# Relay_Board_R2.net
KiCad netlist of a schematic drawn in EAGLE
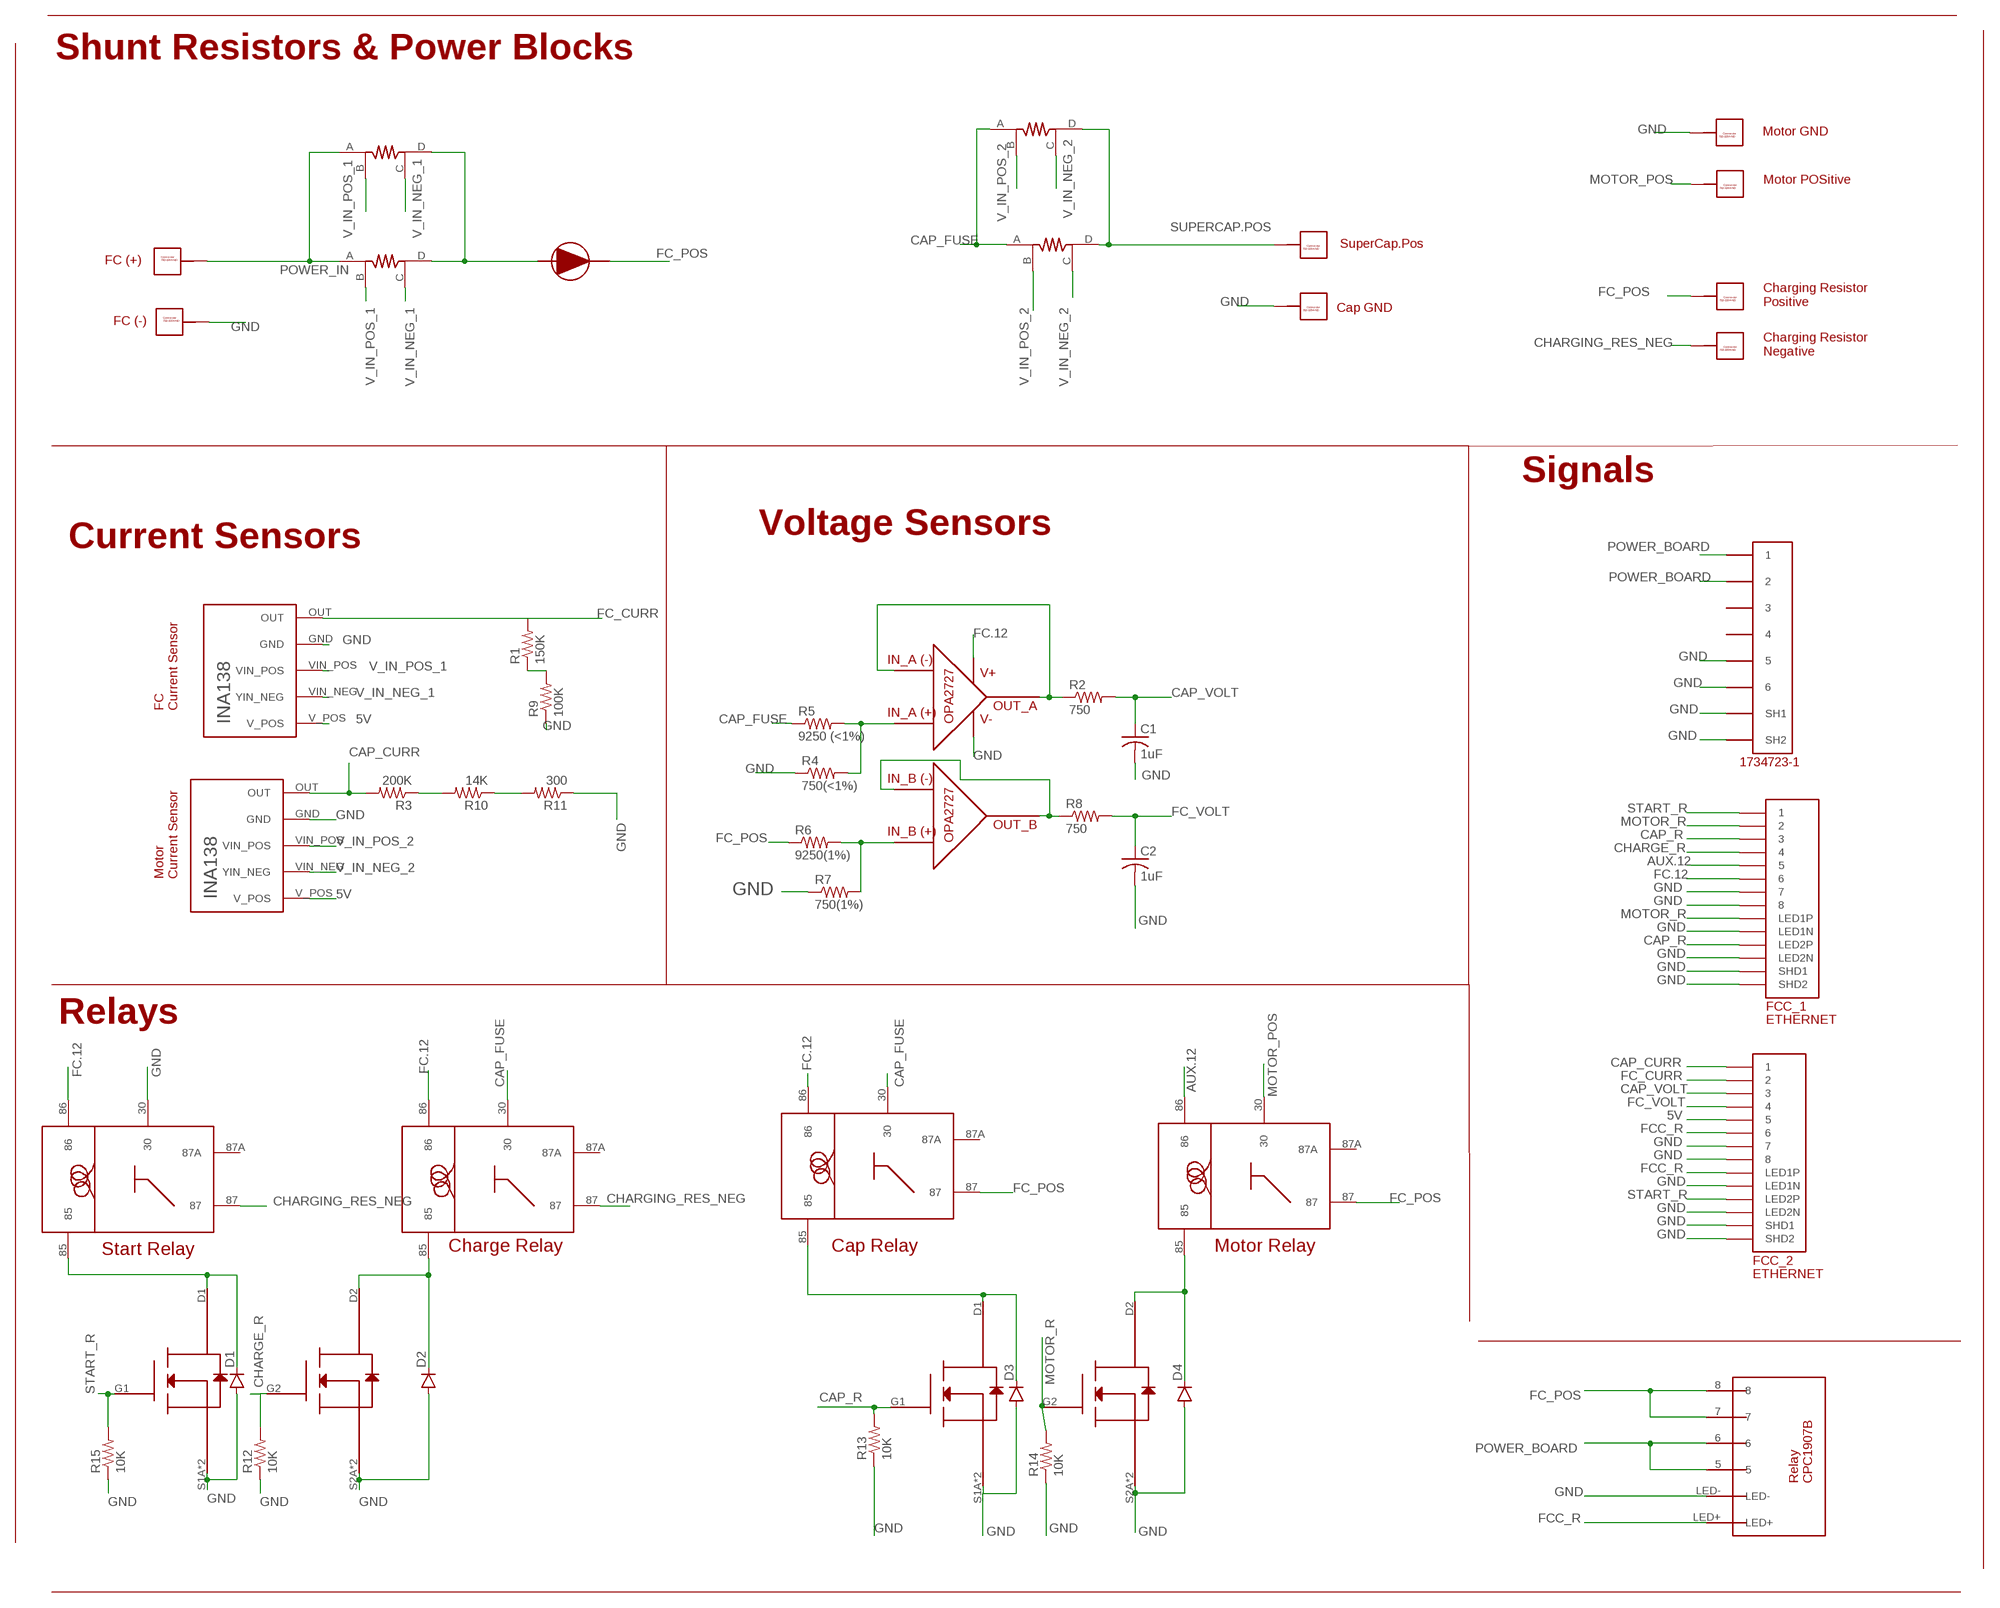
[diagram p0: schematic, sheet 1]

(export (version "E")
  (design (tool "Eeschema 10.0.6"))
  (components
    (comp (ref "C1")
      (value "1uF")
      (footprint "eagle-import:C0805")
      (libsource (lib "eagle-import") (part "C-USC0805"))
    )
    (comp (ref "C2")
      (value "1uF")
      (footprint "eagle-import:C0805")
      (libsource (lib "eagle-import") (part "C-USC0805"))
    )
    (comp (ref "CAP.GND")
      (value "732-3204-ND_CONNECTOR")
      (footprint "eagle-import:732-3204-ND")
      (libsource (lib "eagle-import") (part "732-3204-ND_CONNECTOR"))
    )
    (comp (ref "CAP.POS")
      (value "732-3204-ND_CONNECTOR")
      (footprint "eagle-import:732-3204-ND")
      (libsource (lib "eagle-import") (part "732-3204-ND_CONNECTOR"))
    )
    (comp (ref "CAP.RELAY")
      (value "VCF4-1000")
      (footprint "eagle-import:VCF4-1000")
      (libsource (lib "eagle-import") (part "VCF4-1000"))
    )
    (comp (ref "CAP.SHUNT.1")
      (value "SHUNT_RESISTOR_CSM3637")
      (footprint "eagle-import:CSM3637")
      (libsource (lib "eagle-import") (part "SHUNT_RESISTOR_CSM3637"))
    )
    (comp (ref "CAP.SHUNT.2")
      (value "SHUNT_RESISTOR_CSM3637")
      (footprint "eagle-import:CSM3637")
      (libsource (lib "eagle-import") (part "SHUNT_RESISTOR_CSM3637"))
    )
    (comp (ref "CHARGE_RELAY")
      (value "VCF4-1000")
      (footprint "eagle-import:VCF4-1000")
      (libsource (lib "eagle-import") (part "VCF4-1000"))
    )
    (comp (ref "D1")
      (value "DIODESOD123")
      (footprint "eagle-import:SOD-123")
      (libsource (lib "eagle-import") (part "DIODESOD123"))
    )
    (comp (ref "D2")
      (value "DIODESOD123")
      (footprint "eagle-import:SOD-123")
      (libsource (lib "eagle-import") (part "DIODESOD123"))
    )
    (comp (ref "D3")
      (value "DIODESOD123")
      (footprint "eagle-import:SOD-123")
      (libsource (lib "eagle-import") (part "DIODESOD123"))
    )
    (comp (ref "D4")
      (value "DIODESOD123")
      (footprint "eagle-import:SOD-123")
      (libsource (lib "eagle-import") (part "DIODESOD123"))
    )
    (comp (ref "FC.CURR.SENSOR")
      (value "TI_INA138")
      (footprint "eagle-import:TI_INA138")
      (libsource (lib "eagle-import") (part "TI_INA138"))
    )
    (comp (ref "FC.GND")
      (value "732-3204-ND_CONNECTOR")
      (footprint "eagle-import:732-3204-ND")
      (libsource (lib "eagle-import") (part "732-3204-ND_CONNECTOR"))
    )
    (comp (ref "FC.POS")
      (value "732-3204-ND_CONNECTOR")
      (footprint "eagle-import:732-3204-ND")
      (libsource (lib "eagle-import") (part "732-3204-ND_CONNECTOR"))
    )
    (comp (ref "FC.SHUNT.1")
      (value "SHUNT_RESISTOR_CSM3637")
      (footprint "eagle-import:CSM3637")
      (libsource (lib "eagle-import") (part "SHUNT_RESISTOR_CSM3637"))
    )
    (comp (ref "FC.SHUNT.2")
      (value "SHUNT_RESISTOR_CSM3637")
      (footprint "eagle-import:CSM3637")
      (libsource (lib "eagle-import") (part "SHUNT_RESISTOR_CSM3637"))
    )
    (comp (ref "FCC_1")
      (value "ETHERNET")
      (footprint "eagle-import:A122645-ND")
      (libsource (lib "eagle-import") (part "ETHERNET"))
    )
    (comp (ref "FCC_2")
      (value "ETHERNET")
      (footprint "eagle-import:A122645-ND")
      (libsource (lib "eagle-import") (part "ETHERNET"))
    )
    (comp (ref "FC_DIODE")
      (value "DIODE-APT60S20BG")
      (footprint "eagle-import:DIODE-APT60S20BG")
      (libsource (lib "eagle-import") (part "DIODE-APT60S20BG"))
    )
    (comp (ref "MOTOR.CURR.SENSOR")
      (value "TI_INA138")
      (footprint "eagle-import:TI_INA138")
      (libsource (lib "eagle-import") (part "TI_INA138"))
    )
    (comp (ref "MOTOR.GROUND")
      (value "732-3204-ND_CONNECTOR")
      (footprint "eagle-import:732-3204-ND")
      (libsource (lib "eagle-import") (part "732-3204-ND_CONNECTOR"))
    )
    (comp (ref "MOTOR.POSITIVE")
      (value "732-3204-ND_CONNECTOR")
      (footprint "eagle-import:732-3204-ND")
      (libsource (lib "eagle-import") (part "732-3204-ND_CONNECTOR"))
    )
    (comp (ref "MOTOR.RELAY")
      (value "VCF4-1000")
      (footprint "eagle-import:VCF4-1000")
      (libsource (lib "eagle-import") (part "VCF4-1000"))
    )
    (comp (ref "R1")
      (value "150K")
      (footprint "eagle-import:R0805")
      (libsource (lib "eagle-import") (part "R-US_R0805"))
    )
    (comp (ref "R2")
      (value "750")
      (footprint "eagle-import:R0805")
      (libsource (lib "eagle-import") (part "R-US_R0805"))
    )
    (comp (ref "R3")
      (value "200K")
      (footprint "eagle-import:R0805")
      (libsource (lib "eagle-import") (part "R-US_R0805"))
    )
    (comp (ref "R4")
      (value "750(<1%)")
      (footprint "eagle-import:R0805")
      (libsource (lib "eagle-import") (part "R-US_R0805"))
    )
    (comp (ref "R5")
      (value "9250 (<1%)")
      (footprint "eagle-import:R0805")
      (libsource (lib "eagle-import") (part "R-US_R0805"))
    )
    (comp (ref "R6")
      (value "9250(1%)")
      (footprint "eagle-import:R0805")
      (libsource (lib "eagle-import") (part "R-US_R0805"))
    )
    (comp (ref "R7")
      (value "750(1%)")
      (footprint "eagle-import:R0805")
      (libsource (lib "eagle-import") (part "R-US_R0805"))
    )
    (comp (ref "R8")
      (value "750")
      (footprint "eagle-import:R0805")
      (libsource (lib "eagle-import") (part "R-US_R0805"))
    )
    (comp (ref "R9")
      (value "100K")
      (footprint "eagle-import:R0805")
      (libsource (lib "eagle-import") (part "R-US_R0805"))
    )
    (comp (ref "R10")
      (value "14K")
      (footprint "eagle-import:R0805")
      (libsource (lib "eagle-import") (part "R-US_R0805"))
    )
    (comp (ref "R11")
      (value "300")
      (footprint "eagle-import:R0805")
      (libsource (lib "eagle-import") (part "R-US_R0805"))
    )
    (comp (ref "R12")
      (value "10K")
      (footprint "eagle-import:R0805")
      (libsource (lib "eagle-import") (part "R-US_R0805"))
    )
    (comp (ref "R13")
      (value "10K")
      (footprint "eagle-import:R0805")
      (libsource (lib "eagle-import") (part "R-US_R0805"))
    )
    (comp (ref "R14")
      (value "10K")
      (footprint "eagle-import:R0805")
      (libsource (lib "eagle-import") (part "R-US_R0805"))
    )
    (comp (ref "R15")
      (value "10K")
      (footprint "eagle-import:R0805")
      (libsource (lib "eagle-import") (part "R-US_R0805"))
    )
    (comp (ref "RES.NEG")
      (value "732-3204-ND_CONNECTOR")
      (footprint "eagle-import:732-3204-ND")
      (libsource (lib "eagle-import") (part "732-3204-ND_CONNECTOR"))
    )
    (comp (ref "RES.POS")
      (value "732-3204-ND_CONNECTOR")
      (footprint "eagle-import:732-3204-ND")
      (libsource (lib "eagle-import") (part "732-3204-ND_CONNECTOR"))
    )
    (comp (ref "START.RELAY")
      (value "VCF4-1000")
      (footprint "eagle-import:VCF4-1000")
      (libsource (lib "eagle-import") (part "VCF4-1000"))
    )
    (comp (ref "U$9")
      (value "SI6926ADQ-T1-E3CT-ND_MOSFET")
      (footprint "eagle-import:SI6926ADQ-T1-E3CT-ND_MOSFET")
      (libsource (lib "eagle-import") (part "SI6926ADQ-T1-E3CT-ND_MOSFET"))
    )
    (comp (ref "U$17")
      (value "OP-AMP_OPA2727AIDR")
      (footprint "eagle-import:OP-AMP_OPA2727AIDR")
      (libsource (lib "eagle-import") (part "OP-AMP_OPA2727AIDR"))
    )
    (comp (ref "U$19")
      (value "5555140-6")
      (footprint "eagle-import:1734723-1_RJ11")
      (libsource (lib "eagle-import") (part "5555140-6"))
    )
    (comp (ref "U$22")
      (value "RELAY-CPC1907B")
      (footprint "eagle-import:RELAY-CPC1907B")
      (libsource (lib "eagle-import") (part "RELAY-CPC1907B"))
    )
    (comp (ref "U$25")
      (value "SI6926ADQ-T1-E3CT-ND_MOSFET")
      (footprint "eagle-import:SI6926ADQ-T1-E3CT-ND_MOSFET")
      (libsource (lib "eagle-import") (part "SI6926ADQ-T1-E3CT-ND_MOSFET"))
    )
  )
  (nets
    (net (code "1") (name "/5V") (class "Default")
      (node (ref "FC.CURR.SENSOR") (pin "V_POS") (pinfunction "V_POS_V_POS") (pintype "bidirectional"))
      (node (ref "FCC_2") (pin "P$5") (pinfunction "5_P$5") (pintype "bidirectional"))
      (node (ref "MOTOR.CURR.SENSOR") (pin "V_POS") (pinfunction "V_POS_V_POS") (pintype "bidirectional"))
    )
    (net (code "2") (name "/AUX.12") (class "Default")
      (node (ref "FCC_1") (pin "P$5") (pinfunction "5_P$5") (pintype "bidirectional"))
      (node (ref "MOTOR.RELAY") (pin "86") (pinfunction "86_86") (pintype "bidirectional"))
    )
    (net (code "3") (name "/CAP_CURR") (class "Default")
      (node (ref "FCC_2") (pin "P$1") (pinfunction "1_P$1") (pintype "bidirectional"))
      (node (ref "MOTOR.CURR.SENSOR") (pin "OUT") (pinfunction "OUT_OUT") (pintype "bidirectional"))
      (node (ref "R3") (pin "2") (pinfunction "2_2") (pintype "passive"))
    )
    (net (code "4") (name "/CAP_FUSE") (class "Default")
      (node (ref "CAP.RELAY") (pin "30") (pinfunction "30_30") (pintype "bidirectional"))
      (node (ref "CAP.SHUNT.1") (pin "A") (pinfunction "A_A") (pintype "bidirectional"))
      (node (ref "CAP.SHUNT.2") (pin "A") (pinfunction "A_A") (pintype "bidirectional"))
      (node (ref "CHARGE_RELAY") (pin "30") (pinfunction "30_30") (pintype "bidirectional"))
      (node (ref "R5") (pin "1") (pinfunction "1_1") (pintype "passive"))
    )
    (net (code "5") (name "/CAP_R") (class "Default")
      (node (ref "FCC_1") (pin "P$12") (pinfunction "LED2P_P$12") (pintype "bidirectional"))
      (node (ref "FCC_1") (pin "P$3") (pinfunction "3_P$3") (pintype "bidirectional"))
      (node (ref "R13") (pin "2") (pinfunction "2_2") (pintype "passive"))
      (node (ref "U$9") (pin "G1") (pinfunction "G1_G1") (pintype "bidirectional"))
    )
    (net (code "6") (name "/CAP_VOLT") (class "Default")
      (node (ref "C1") (pin "1") (pinfunction "1_1") (pintype "passive"))
      (node (ref "FCC_2") (pin "P$3") (pinfunction "3_P$3") (pintype "bidirectional"))
      (node (ref "R2") (pin "2") (pinfunction "2_2") (pintype "passive"))
    )
    (net (code "7") (name "/CHARGE_R") (class "Default")
      (node (ref "FCC_1") (pin "P$4") (pinfunction "4_P$4") (pintype "bidirectional"))
      (node (ref "R12") (pin "2") (pinfunction "2_2") (pintype "passive"))
      (node (ref "U$25") (pin "G2") (pinfunction "G2_G2") (pintype "bidirectional"))
    )
    (net (code "8") (name "/CHARGING_RES_NEG") (class "Default")
      (node (ref "CHARGE_RELAY") (pin "87") (pinfunction "87_87") (pintype "bidirectional"))
      (node (ref "RES.NEG") (pin "P$1") (pinfunction "P$1_P$1") (pintype "bidirectional"))
      (node (ref "RES.NEG") (pin "P$10") (pinfunction "P$1_P$10") (pintype "bidirectional"))
      (node (ref "RES.NEG") (pin "P$2") (pinfunction "P$1_P$2") (pintype "bidirectional"))
      (node (ref "RES.NEG") (pin "P$3") (pinfunction "P$1_P$3") (pintype "bidirectional"))
      (node (ref "RES.NEG") (pin "P$4") (pinfunction "P$1_P$4") (pintype "bidirectional"))
      (node (ref "RES.NEG") (pin "P$5") (pinfunction "P$1_P$5") (pintype "bidirectional"))
      (node (ref "RES.NEG") (pin "P$6") (pinfunction "P$1_P$6") (pintype "bidirectional"))
      (node (ref "RES.NEG") (pin "P$7") (pinfunction "P$1_P$7") (pintype "bidirectional"))
      (node (ref "RES.NEG") (pin "P$8") (pinfunction "P$1_P$8") (pintype "bidirectional"))
      (node (ref "RES.NEG") (pin "P$9") (pinfunction "P$1_P$9") (pintype "bidirectional"))
      (node (ref "START.RELAY") (pin "87") (pinfunction "87_87") (pintype "bidirectional"))
    )
    (net (code "9") (name "/FC.12") (class "Default")
      (node (ref "CAP.RELAY") (pin "86") (pinfunction "86_86") (pintype "bidirectional"))
      (node (ref "CHARGE_RELAY") (pin "86") (pinfunction "86_86") (pintype "bidirectional"))
      (node (ref "FCC_1") (pin "P$6") (pinfunction "6_P$6") (pintype "bidirectional"))
      (node (ref "START.RELAY") (pin "86") (pinfunction "86_86") (pintype "bidirectional"))
      (node (ref "U$17") (pin "V+") (pinfunction "V+_V+") (pintype "bidirectional"))
    )
    (net (code "10") (name "/FCC_R") (class "Default")
      (node (ref "FCC_2") (pin "P$10") (pinfunction "LED1P_P$10") (pintype "bidirectional"))
      (node (ref "FCC_2") (pin "P$6") (pinfunction "6_P$6") (pintype "bidirectional"))
      (node (ref "U$22") (pin "LED+") (pinfunction "LED+_LED+") (pintype "bidirectional"))
    )
    (net (code "11") (name "/FC_CURR") (class "Default")
      (node (ref "FC.CURR.SENSOR") (pin "OUT") (pinfunction "OUT_OUT") (pintype "bidirectional"))
      (node (ref "FCC_2") (pin "P$2") (pinfunction "2_P$2") (pintype "bidirectional"))
      (node (ref "R1") (pin "2") (pinfunction "2_2") (pintype "passive"))
    )
    (net (code "12") (name "/FC_POS") (class "Default")
      (node (ref "CAP.RELAY") (pin "87") (pinfunction "87_87") (pintype "bidirectional"))
      (node (ref "FC_DIODE") (pin "CATHODE") (pinfunction "CATHODE_CATHODE") (pintype "output"))
      (node (ref "MOTOR.RELAY") (pin "87") (pinfunction "87_87") (pintype "bidirectional"))
      (node (ref "R6") (pin "1") (pinfunction "1_1") (pintype "passive"))
      (node (ref "RES.POS") (pin "P$1") (pinfunction "P$1_P$1") (pintype "bidirectional"))
      (node (ref "RES.POS") (pin "P$10") (pinfunction "P$1_P$10") (pintype "bidirectional"))
      (node (ref "RES.POS") (pin "P$2") (pinfunction "P$1_P$2") (pintype "bidirectional"))
      (node (ref "RES.POS") (pin "P$3") (pinfunction "P$1_P$3") (pintype "bidirectional"))
      (node (ref "RES.POS") (pin "P$4") (pinfunction "P$1_P$4") (pintype "bidirectional"))
      (node (ref "RES.POS") (pin "P$5") (pinfunction "P$1_P$5") (pintype "bidirectional"))
      (node (ref "RES.POS") (pin "P$6") (pinfunction "P$1_P$6") (pintype "bidirectional"))
      (node (ref "RES.POS") (pin "P$7") (pinfunction "P$1_P$7") (pintype "bidirectional"))
      (node (ref "RES.POS") (pin "P$8") (pinfunction "P$1_P$8") (pintype "bidirectional"))
      (node (ref "RES.POS") (pin "P$9") (pinfunction "P$1_P$9") (pintype "bidirectional"))
      (node (ref "U$22") (pin "7") (pinfunction "7_7") (pintype "bidirectional"))
      (node (ref "U$22") (pin "8") (pinfunction "8_8") (pintype "bidirectional"))
    )
    (net (code "13") (name "/FC_VOLT") (class "Default")
      (node (ref "C2") (pin "1") (pinfunction "1_1") (pintype "passive"))
      (node (ref "FCC_2") (pin "P$4") (pinfunction "4_P$4") (pintype "bidirectional"))
      (node (ref "R8") (pin "2") (pinfunction "2_2") (pintype "passive"))
    )
    (net (code "14") (name "/GND") (class "Default")
      (node (ref "C1") (pin "2") (pinfunction "2_2") (pintype "passive"))
      (node (ref "C2") (pin "2") (pinfunction "2_2") (pintype "passive"))
      (node (ref "CAP.GND") (pin "P$1") (pinfunction "P$1_P$1") (pintype "bidirectional"))
      (node (ref "CAP.GND") (pin "P$10") (pinfunction "P$1_P$10") (pintype "bidirectional"))
      (node (ref "CAP.GND") (pin "P$2") (pinfunction "P$1_P$2") (pintype "bidirectional"))
      (node (ref "CAP.GND") (pin "P$3") (pinfunction "P$1_P$3") (pintype "bidirectional"))
      (node (ref "CAP.GND") (pin "P$4") (pinfunction "P$1_P$4") (pintype "bidirectional"))
      (node (ref "CAP.GND") (pin "P$5") (pinfunction "P$1_P$5") (pintype "bidirectional"))
      (node (ref "CAP.GND") (pin "P$6") (pinfunction "P$1_P$6") (pintype "bidirectional"))
      (node (ref "CAP.GND") (pin "P$7") (pinfunction "P$1_P$7") (pintype "bidirectional"))
      (node (ref "CAP.GND") (pin "P$8") (pinfunction "P$1_P$8") (pintype "bidirectional"))
      (node (ref "CAP.GND") (pin "P$9") (pinfunction "P$1_P$9") (pintype "bidirectional"))
      (node (ref "D1") (pin "A") (pinfunction "A_A") (pintype "passive"))
      (node (ref "D2") (pin "A") (pinfunction "A_A") (pintype "passive"))
      (node (ref "D3") (pin "A") (pinfunction "A_A") (pintype "passive"))
      (node (ref "D4") (pin "A") (pinfunction "A_A") (pintype "passive"))
      (node (ref "FC.CURR.SENSOR") (pin "GND") (pinfunction "GND_GND") (pintype "bidirectional"))
      (node (ref "FC.GND") (pin "P$1") (pinfunction "P$1_P$1") (pintype "bidirectional"))
      (node (ref "FC.GND") (pin "P$10") (pinfunction "P$1_P$10") (pintype "bidirectional"))
      (node (ref "FC.GND") (pin "P$2") (pinfunction "P$1_P$2") (pintype "bidirectional"))
      (node (ref "FC.GND") (pin "P$3") (pinfunction "P$1_P$3") (pintype "bidirectional"))
      (node (ref "FC.GND") (pin "P$4") (pinfunction "P$1_P$4") (pintype "bidirectional"))
      (node (ref "FC.GND") (pin "P$5") (pinfunction "P$1_P$5") (pintype "bidirectional"))
      (node (ref "FC.GND") (pin "P$6") (pinfunction "P$1_P$6") (pintype "bidirectional"))
      (node (ref "FC.GND") (pin "P$7") (pinfunction "P$1_P$7") (pintype "bidirectional"))
      (node (ref "FC.GND") (pin "P$8") (pinfunction "P$1_P$8") (pintype "bidirectional"))
      (node (ref "FC.GND") (pin "P$9") (pinfunction "P$1_P$9") (pintype "bidirectional"))
      (node (ref "FCC_1") (pin "P$11") (pinfunction "LED2N_P$11") (pintype "bidirectional"))
      (node (ref "FCC_1") (pin "P$13") (pinfunction "SHD1_P$13") (pintype "bidirectional"))
      (node (ref "FCC_1") (pin "P$14") (pinfunction "SHD2_P$14") (pintype "bidirectional"))
      (node (ref "FCC_1") (pin "P$7") (pinfunction "7_P$7") (pintype "bidirectional"))
      (node (ref "FCC_1") (pin "P$8") (pinfunction "8_P$8") (pintype "bidirectional"))
      (node (ref "FCC_1") (pin "P$9") (pinfunction "LED1N_P$9") (pintype "bidirectional"))
      (node (ref "FCC_2") (pin "P$11") (pinfunction "LED2N_P$11") (pintype "bidirectional"))
      (node (ref "FCC_2") (pin "P$13") (pinfunction "SHD1_P$13") (pintype "bidirectional"))
      (node (ref "FCC_2") (pin "P$14") (pinfunction "SHD2_P$14") (pintype "bidirectional"))
      (node (ref "FCC_2") (pin "P$7") (pinfunction "7_P$7") (pintype "bidirectional"))
      (node (ref "FCC_2") (pin "P$8") (pinfunction "8_P$8") (pintype "bidirectional"))
      (node (ref "FCC_2") (pin "P$9") (pinfunction "LED1N_P$9") (pintype "bidirectional"))
      (node (ref "MOTOR.CURR.SENSOR") (pin "GND") (pinfunction "GND_GND") (pintype "bidirectional"))
      (node (ref "MOTOR.GROUND") (pin "P$1") (pinfunction "P$1_P$1") (pintype "bidirectional"))
      (node (ref "MOTOR.GROUND") (pin "P$10") (pinfunction "P$1_P$10") (pintype "bidirectional"))
      (node (ref "MOTOR.GROUND") (pin "P$2") (pinfunction "P$1_P$2") (pintype "bidirectional"))
      (node (ref "MOTOR.GROUND") (pin "P$3") (pinfunction "P$1_P$3") (pintype "bidirectional"))
      (node (ref "MOTOR.GROUND") (pin "P$4") (pinfunction "P$1_P$4") (pintype "bidirectional"))
      (node (ref "MOTOR.GROUND") (pin "P$5") (pinfunction "P$1_P$5") (pintype "bidirectional"))
      (node (ref "MOTOR.GROUND") (pin "P$6") (pinfunction "P$1_P$6") (pintype "bidirectional"))
      (node (ref "MOTOR.GROUND") (pin "P$7") (pinfunction "P$1_P$7") (pintype "bidirectional"))
      (node (ref "MOTOR.GROUND") (pin "P$8") (pinfunction "P$1_P$8") (pintype "bidirectional"))
      (node (ref "MOTOR.GROUND") (pin "P$9") (pinfunction "P$1_P$9") (pintype "bidirectional"))
      (node (ref "R11") (pin "1") (pinfunction "1_1") (pintype "passive"))
      (node (ref "R12") (pin "1") (pinfunction "1_1") (pintype "passive"))
      (node (ref "R13") (pin "1") (pinfunction "1_1") (pintype "passive"))
      (node (ref "R14") (pin "1") (pinfunction "1_1") (pintype "passive"))
      (node (ref "R15") (pin "1") (pinfunction "1_1") (pintype "passive"))
      (node (ref "R4") (pin "1") (pinfunction "1_1") (pintype "passive"))
      (node (ref "R7") (pin "1") (pinfunction "1_1") (pintype "passive"))
      (node (ref "R9") (pin "1") (pinfunction "1_1") (pintype "passive"))
      (node (ref "START.RELAY") (pin "30") (pinfunction "30_30") (pintype "bidirectional"))
      (node (ref "U$17") (pin "V-") (pinfunction "V-_V-") (pintype "bidirectional"))
      (node (ref "U$19") (pin "5") (pinfunction "5_5") (pintype "bidirectional"))
      (node (ref "U$19") (pin "6") (pinfunction "6_6") (pintype "bidirectional"))
      (node (ref "U$19") (pin "SH1") (pinfunction "SH1_SH1") (pintype "bidirectional"))
      (node (ref "U$19") (pin "SH2") (pinfunction "SH2_SH2") (pintype "bidirectional"))
      (node (ref "U$22") (pin "LED-") (pinfunction "LED-_LED-") (pintype "bidirectional"))
      (node (ref "U$25") (pin "S1A") (pinfunction "S1_S1A") (pintype "bidirectional"))
      (node (ref "U$25") (pin "S1B") (pinfunction "S1_S1B") (pintype "bidirectional"))
      (node (ref "U$25") (pin "S2A") (pinfunction "S2_S2A") (pintype "bidirectional"))
      (node (ref "U$25") (pin "S2B") (pinfunction "S2_S2B") (pintype "bidirectional"))
      (node (ref "U$9") (pin "S1A") (pinfunction "S1_S1A") (pintype "bidirectional"))
      (node (ref "U$9") (pin "S1B") (pinfunction "S1_S1B") (pintype "bidirectional"))
      (node (ref "U$9") (pin "S2A") (pinfunction "S2_S2A") (pintype "bidirectional"))
      (node (ref "U$9") (pin "S2B") (pinfunction "S2_S2B") (pintype "bidirectional"))
    )
    (net (code "15") (name "/MOTOR_POS") (class "Default")
      (node (ref "MOTOR.POSITIVE") (pin "P$1") (pinfunction "P$1_P$1") (pintype "bidirectional"))
      (node (ref "MOTOR.POSITIVE") (pin "P$10") (pinfunction "P$1_P$10") (pintype "bidirectional"))
      (node (ref "MOTOR.POSITIVE") (pin "P$2") (pinfunction "P$1_P$2") (pintype "bidirectional"))
      (node (ref "MOTOR.POSITIVE") (pin "P$3") (pinfunction "P$1_P$3") (pintype "bidirectional"))
      (node (ref "MOTOR.POSITIVE") (pin "P$4") (pinfunction "P$1_P$4") (pintype "bidirectional"))
      (node (ref "MOTOR.POSITIVE") (pin "P$5") (pinfunction "P$1_P$5") (pintype "bidirectional"))
      (node (ref "MOTOR.POSITIVE") (pin "P$6") (pinfunction "P$1_P$6") (pintype "bidirectional"))
      (node (ref "MOTOR.POSITIVE") (pin "P$7") (pinfunction "P$1_P$7") (pintype "bidirectional"))
      (node (ref "MOTOR.POSITIVE") (pin "P$8") (pinfunction "P$1_P$8") (pintype "bidirectional"))
      (node (ref "MOTOR.POSITIVE") (pin "P$9") (pinfunction "P$1_P$9") (pintype "bidirectional"))
      (node (ref "MOTOR.RELAY") (pin "30") (pinfunction "30_30") (pintype "bidirectional"))
    )
    (net (code "16") (name "/MOTOR_R") (class "Default")
      (node (ref "FCC_1") (pin "P$10") (pinfunction "LED1P_P$10") (pintype "bidirectional"))
      (node (ref "FCC_1") (pin "P$2") (pinfunction "2_P$2") (pintype "bidirectional"))
      (node (ref "R14") (pin "2") (pinfunction "2_2") (pintype "passive"))
      (node (ref "U$9") (pin "G2") (pinfunction "G2_G2") (pintype "bidirectional"))
    )
    (net (code "17") (name "/POWER_BOARD") (class "Default")
      (node (ref "U$19") (pin "1") (pinfunction "1_1") (pintype "bidirectional"))
      (node (ref "U$19") (pin "2") (pinfunction "2_2") (pintype "bidirectional"))
      (node (ref "U$22") (pin "5") (pinfunction "5_5") (pintype "bidirectional"))
      (node (ref "U$22") (pin "6") (pinfunction "6_6") (pintype "bidirectional"))
    )
    (net (code "18") (name "/POWER_IN") (class "Default")
      (node (ref "FC.POS") (pin "P$1") (pinfunction "P$1_P$1") (pintype "bidirectional"))
      (node (ref "FC.POS") (pin "P$10") (pinfunction "P$1_P$10") (pintype "bidirectional"))
      (node (ref "FC.POS") (pin "P$2") (pinfunction "P$1_P$2") (pintype "bidirectional"))
      (node (ref "FC.POS") (pin "P$3") (pinfunction "P$1_P$3") (pintype "bidirectional"))
      (node (ref "FC.POS") (pin "P$4") (pinfunction "P$1_P$4") (pintype "bidirectional"))
      (node (ref "FC.POS") (pin "P$5") (pinfunction "P$1_P$5") (pintype "bidirectional"))
      (node (ref "FC.POS") (pin "P$6") (pinfunction "P$1_P$6") (pintype "bidirectional"))
      (node (ref "FC.POS") (pin "P$7") (pinfunction "P$1_P$7") (pintype "bidirectional"))
      (node (ref "FC.POS") (pin "P$8") (pinfunction "P$1_P$8") (pintype "bidirectional"))
      (node (ref "FC.POS") (pin "P$9") (pinfunction "P$1_P$9") (pintype "bidirectional"))
      (node (ref "FC.SHUNT.1") (pin "A") (pinfunction "A_A") (pintype "bidirectional"))
      (node (ref "FC.SHUNT.2") (pin "A") (pinfunction "A_A") (pintype "bidirectional"))
    )
    (net (code "19") (name "/START_R") (class "Default")
      (node (ref "FCC_1") (pin "P$1") (pinfunction "1_P$1") (pintype "bidirectional"))
      (node (ref "FCC_2") (pin "P$12") (pinfunction "LED2P_P$12") (pintype "bidirectional"))
      (node (ref "R15") (pin "2") (pinfunction "2_2") (pintype "passive"))
      (node (ref "U$25") (pin "G1") (pinfunction "G1_G1") (pintype "bidirectional"))
    )
    (net (code "20") (name "/SUPERCAP.POS") (class "Default")
      (node (ref "CAP.POS") (pin "P$1") (pinfunction "P$1_P$1") (pintype "bidirectional"))
      (node (ref "CAP.POS") (pin "P$10") (pinfunction "P$1_P$10") (pintype "bidirectional"))
      (node (ref "CAP.POS") (pin "P$2") (pinfunction "P$1_P$2") (pintype "bidirectional"))
      (node (ref "CAP.POS") (pin "P$3") (pinfunction "P$1_P$3") (pintype "bidirectional"))
      (node (ref "CAP.POS") (pin "P$4") (pinfunction "P$1_P$4") (pintype "bidirectional"))
      (node (ref "CAP.POS") (pin "P$5") (pinfunction "P$1_P$5") (pintype "bidirectional"))
      (node (ref "CAP.POS") (pin "P$6") (pinfunction "P$1_P$6") (pintype "bidirectional"))
      (node (ref "CAP.POS") (pin "P$7") (pinfunction "P$1_P$7") (pintype "bidirectional"))
      (node (ref "CAP.POS") (pin "P$8") (pinfunction "P$1_P$8") (pintype "bidirectional"))
      (node (ref "CAP.POS") (pin "P$9") (pinfunction "P$1_P$9") (pintype "bidirectional"))
      (node (ref "CAP.SHUNT.1") (pin "D") (pinfunction "D_D") (pintype "bidirectional"))
      (node (ref "CAP.SHUNT.2") (pin "D") (pinfunction "D_D") (pintype "bidirectional"))
    )
    (net (code "21") (name "/V_IN_NEG_1") (class "Default")
      (node (ref "FC.CURR.SENSOR") (pin "VIN_NEG") (pinfunction "YIN_NEG_VIN_NEG") (pintype "bidirectional"))
      (node (ref "FC.SHUNT.1") (pin "C") (pinfunction "C_C") (pintype "bidirectional"))
      (node (ref "FC.SHUNT.2") (pin "C") (pinfunction "C_C") (pintype "bidirectional"))
    )
    (net (code "22") (name "/V_IN_NEG_2") (class "Default")
      (node (ref "CAP.SHUNT.1") (pin "C") (pinfunction "C_C") (pintype "bidirectional"))
      (node (ref "CAP.SHUNT.2") (pin "C") (pinfunction "C_C") (pintype "bidirectional"))
      (node (ref "MOTOR.CURR.SENSOR") (pin "VIN_NEG") (pinfunction "YIN_NEG_VIN_NEG") (pintype "bidirectional"))
    )
    (net (code "23") (name "/V_IN_POS_1") (class "Default")
      (node (ref "FC.CURR.SENSOR") (pin "VIN_POS") (pinfunction "VIN_POS_VIN_POS") (pintype "bidirectional"))
      (node (ref "FC.SHUNT.1") (pin "B") (pinfunction "B_B") (pintype "bidirectional"))
      (node (ref "FC.SHUNT.2") (pin "B") (pinfunction "B_B") (pintype "bidirectional"))
    )
    (net (code "24") (name "/V_IN_POS_2") (class "Default")
      (node (ref "CAP.SHUNT.1") (pin "B") (pinfunction "B_B") (pintype "bidirectional"))
      (node (ref "CAP.SHUNT.2") (pin "B") (pinfunction "B_B") (pintype "bidirectional"))
      (node (ref "MOTOR.CURR.SENSOR") (pin "VIN_POS") (pinfunction "VIN_POS_VIN_POS") (pintype "bidirectional"))
    )
    (net (code "25") (name "Net-(CAP.RELAY-Pad85)") (class "Default")
      (node (ref "CAP.RELAY") (pin "85") (pinfunction "85_85") (pintype "bidirectional"))
      (node (ref "D3") (pin "C") (pinfunction "C_C") (pintype "passive"))
      (node (ref "U$9") (pin "D1") (pinfunction "D1_D1") (pintype "bidirectional"))
    )
    (net (code "26") (name "Net-(CHARGE_RELAY-Pad85)") (class "Default")
      (node (ref "CHARGE_RELAY") (pin "85") (pinfunction "85_85") (pintype "bidirectional"))
      (node (ref "D2") (pin "C") (pinfunction "C_C") (pintype "passive"))
      (node (ref "U$25") (pin "D2") (pinfunction "D2_D2") (pintype "bidirectional"))
    )
    (net (code "27") (name "Net-(D1-PadC)") (class "Default")
      (node (ref "D1") (pin "C") (pinfunction "C_C") (pintype "passive"))
      (node (ref "START.RELAY") (pin "85") (pinfunction "85_85") (pintype "bidirectional"))
      (node (ref "U$25") (pin "D1") (pinfunction "D1_D1") (pintype "bidirectional"))
    )
    (net (code "28") (name "Net-(D4-PadC)") (class "Default")
      (node (ref "D4") (pin "C") (pinfunction "C_C") (pintype "passive"))
      (node (ref "MOTOR.RELAY") (pin "85") (pinfunction "85_85") (pintype "bidirectional"))
      (node (ref "U$9") (pin "D2") (pinfunction "D2_D2") (pintype "bidirectional"))
    )
    (net (code "29") (name "Net-(FC.SHUNT.1-PadD)") (class "Default")
      (node (ref "FC.SHUNT.1") (pin "D") (pinfunction "D_D") (pintype "bidirectional"))
      (node (ref "FC.SHUNT.2") (pin "D") (pinfunction "D_D") (pintype "bidirectional"))
      (node (ref "FC_DIODE") (pin "ANODE") (pinfunction "ANODE_ANODE") (pintype "input"))
    )
    (net (code "30") (name "Net-(R1-Pad1)") (class "Default")
      (node (ref "R1") (pin "1") (pinfunction "1_1") (pintype "passive"))
      (node (ref "R9") (pin "2") (pinfunction "2_2") (pintype "passive"))
    )
    (net (code "31") (name "Net-(R2-Pad1)") (class "Default")
      (node (ref "R2") (pin "1") (pinfunction "1_1") (pintype "passive"))
      (node (ref "U$17") (pin "IN_A-") (pinfunction "IN_A-_IN_A-") (pintype "bidirectional"))
      (node (ref "U$17") (pin "OUT_A") (pinfunction "OUT_A_OUT_A") (pintype "bidirectional"))
    )
    (net (code "32") (name "Net-(R4-Pad2)") (class "Default")
      (node (ref "R4") (pin "2") (pinfunction "2_2") (pintype "passive"))
      (node (ref "R5") (pin "2") (pinfunction "2_2") (pintype "passive"))
      (node (ref "U$17") (pin "IN_A+") (pinfunction "IN_A+_IN_A+") (pintype "bidirectional"))
    )
    (net (code "33") (name "Net-(R6-Pad2)") (class "Default")
      (node (ref "R6") (pin "2") (pinfunction "2_2") (pintype "passive"))
      (node (ref "R7") (pin "2") (pinfunction "2_2") (pintype "passive"))
      (node (ref "U$17") (pin "IN_B+") (pinfunction "IN_B+_IN_B+") (pintype "bidirectional"))
    )
    (net (code "34") (name "Net-(R8-Pad1)") (class "Default")
      (node (ref "R8") (pin "1") (pinfunction "1_1") (pintype "passive"))
      (node (ref "U$17") (pin "IN_B-") (pinfunction "IN_B-_IN_B-") (pintype "bidirectional"))
      (node (ref "U$17") (pin "OUT_B") (pinfunction "OUT_B_OUT_B") (pintype "bidirectional"))
    )
    (net (code "35") (name "Net-(R10-Pad1)") (class "Default")
      (node (ref "R10") (pin "1") (pinfunction "1_1") (pintype "passive"))
      (node (ref "R11") (pin "2") (pinfunction "2_2") (pintype "passive"))
    )
    (net (code "36") (name "Net-(R10-Pad2)") (class "Default")
      (node (ref "R10") (pin "2") (pinfunction "2_2") (pintype "passive"))
      (node (ref "R3") (pin "1") (pinfunction "1_1") (pintype "passive"))
    )
    (net (code "37") (name "unconnected-(CAP.RELAY-Pad87A)") (class "Default")
      (node (ref "CAP.RELAY") (pin "87A") (pinfunction "87A_87A") (pintype "bidirectional"))
    )
    (net (code "38") (name "unconnected-(CHARGE_RELAY-Pad87A)") (class "Default")
      (node (ref "CHARGE_RELAY") (pin "87A") (pinfunction "87A_87A") (pintype "bidirectional"))
    )
    (net (code "39") (name "unconnected-(MOTOR.RELAY-Pad87A)") (class "Default")
      (node (ref "MOTOR.RELAY") (pin "87A") (pinfunction "87A_87A") (pintype "bidirectional"))
    )
    (net (code "40") (name "unconnected-(START.RELAY-Pad87A)") (class "Default")
      (node (ref "START.RELAY") (pin "87A") (pinfunction "87A_87A") (pintype "bidirectional"))
    )
    (net (code "41") (name "unconnected-(U$19-Pad3)") (class "Default")
      (node (ref "U$19") (pin "3") (pinfunction "3_3") (pintype "bidirectional"))
    )
    (net (code "42") (name "unconnected-(U$19-Pad4)") (class "Default")
      (node (ref "U$19") (pin "4") (pinfunction "4_4") (pintype "bidirectional"))
    )
  )
)
